# sch-contacts.net
KiCad netlist of a schematic drawn in Altium Designer
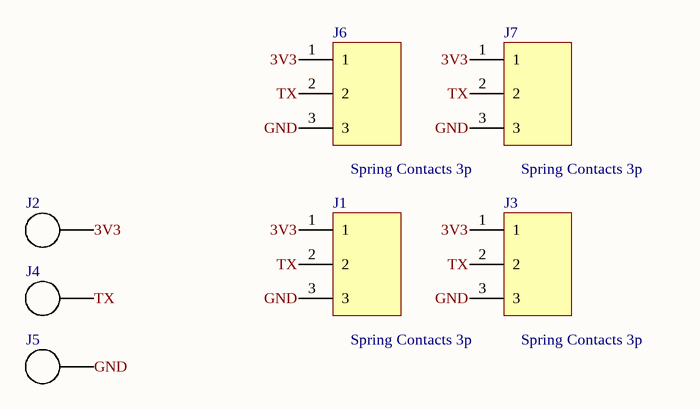
[diagram p0: sch-contacts.SchDoc]

(export (version "E")
  (design (tool "Eeschema 10.0.6"))
  (components
    (comp (ref "J1")
      (value "Spring Contacts 3p")
      (footprint "70ABJ-3-M0E")
      (description "Spring loaded electrical contacts")
      (libsource (lib "slip-ring") (part "‎70ABJ-3-M0E‎"))
    )
    (comp (ref "J2")
      (value "pad single")
      (footprint "PAD_SING")
      (libsource (lib "slip-ring") (part "PAD-SING"))
    )
    (comp (ref "J3")
      (value "Spring Contacts 3p")
      (footprint "70ABJ-3-M0E")
      (description "Spring loaded electrical contacts")
      (libsource (lib "slip-ring") (part "‎70ABJ-3-M0E‎"))
    )
    (comp (ref "J4")
      (value "pad single")
      (footprint "PAD_SING")
      (libsource (lib "slip-ring") (part "PAD-SING"))
    )
    (comp (ref "J5")
      (value "pad single")
      (footprint "PAD_SING")
      (libsource (lib "slip-ring") (part "PAD-SING"))
    )
    (comp (ref "J6")
      (value "Spring Contacts 3p")
      (footprint "70ABJ-3-M0E")
      (description "Spring loaded electrical contacts")
      (libsource (lib "slip-ring") (part "‎70ABJ-3-M0E‎"))
    )
    (comp (ref "J7")
      (value "Spring Contacts 3p")
      (footprint "70ABJ-3-M0E")
      (description "Spring loaded electrical contacts")
      (libsource (lib "slip-ring") (part "‎70ABJ-3-M0E‎"))
    )
  )
  (nets
    (net (code "1") (name "/3V3") (class "Default")
      (node (ref "J1") (pin "1") (pinfunction "1_1") (pintype "power_in"))
      (node (ref "J1") (pin "6") (pinfunction "6_6") (pintype "power_in"))
      (node (ref "J2") (pin "1") (pinfunction "1_1") (pintype "power_in"))
      (node (ref "J3") (pin "1") (pinfunction "1_1") (pintype "power_in"))
      (node (ref "J3") (pin "6") (pinfunction "6_6") (pintype "power_in"))
      (node (ref "J6") (pin "1") (pinfunction "1_1") (pintype "power_in"))
      (node (ref "J6") (pin "6") (pinfunction "6_6") (pintype "power_in"))
      (node (ref "J7") (pin "1") (pinfunction "1_1") (pintype "power_in"))
      (node (ref "J7") (pin "6") (pinfunction "6_6") (pintype "power_in"))
    )
    (net (code "2") (name "/GND") (class "Default")
      (node (ref "J1") (pin "3") (pinfunction "3_3") (pintype "power_in"))
      (node (ref "J1") (pin "4") (pinfunction "4_4") (pintype "power_in"))
      (node (ref "J3") (pin "3") (pinfunction "3_3") (pintype "power_in"))
      (node (ref "J3") (pin "4") (pinfunction "4_4") (pintype "power_in"))
      (node (ref "J5") (pin "1") (pinfunction "1_1") (pintype "power_in"))
      (node (ref "J6") (pin "3") (pinfunction "3_3") (pintype "power_in"))
      (node (ref "J6") (pin "4") (pinfunction "4_4") (pintype "power_in"))
      (node (ref "J7") (pin "3") (pinfunction "3_3") (pintype "power_in"))
      (node (ref "J7") (pin "4") (pinfunction "4_4") (pintype "power_in"))
    )
    (net (code "3") (name "/TX") (class "Default")
      (node (ref "J1") (pin "2") (pinfunction "2_2") (pintype "power_in"))
      (node (ref "J1") (pin "5") (pinfunction "5_5") (pintype "power_in"))
      (node (ref "J3") (pin "2") (pinfunction "2_2") (pintype "power_in"))
      (node (ref "J3") (pin "5") (pinfunction "5_5") (pintype "power_in"))
      (node (ref "J4") (pin "1") (pinfunction "1_1") (pintype "power_in"))
      (node (ref "J6") (pin "2") (pinfunction "2_2") (pintype "power_in"))
      (node (ref "J6") (pin "5") (pinfunction "5_5") (pintype "power_in"))
      (node (ref "J7") (pin "2") (pinfunction "2_2") (pintype "power_in"))
      (node (ref "J7") (pin "5") (pinfunction "5_5") (pintype "power_in"))
    )
  )
)
